# rev02_8.net
KiCad netlist of a schematic drawn in Altium Designer
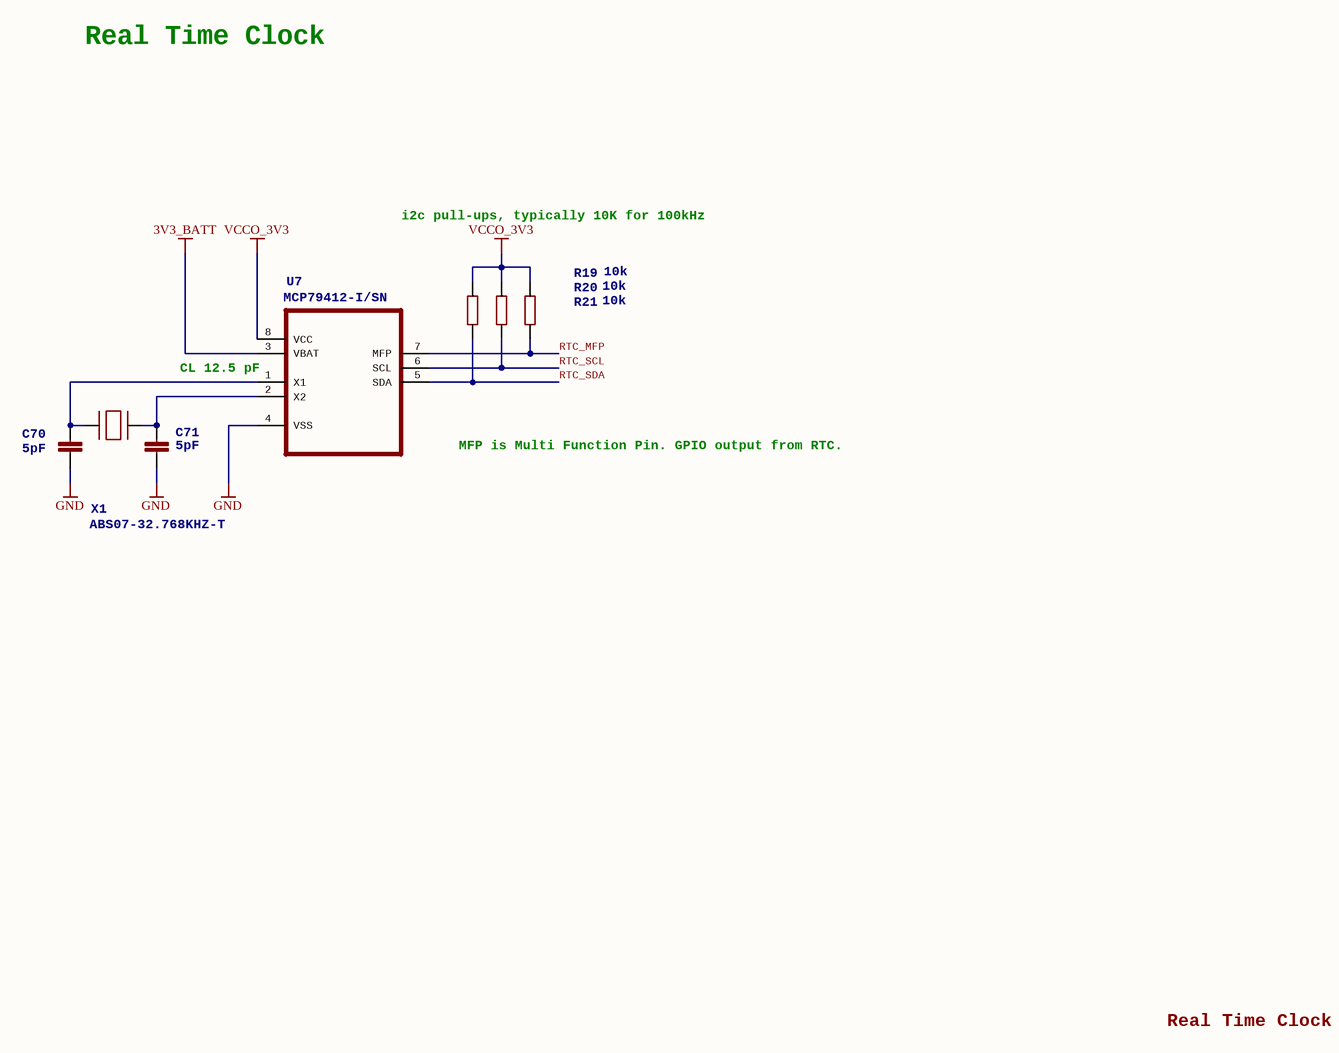
[diagram p0: rev02_8.SchDoc]

(export (version "E")
  (design (tool "Eeschema 10.0.6"))
  (components
    (comp (ref "C70")
      (value "5pF")
      (footprint "C_0402")
      (description "0402 CAPACITOR")
      (libsource (lib "resistor") (part "C-EUC0402"))
    )
    (comp (ref "C71")
      (value "5pF")
      (footprint "C_0402")
      (description "0402 CAPACITOR")
      (libsource (lib "resistor") (part "C-EUC0402"))
    )
    (comp (ref "R19")
      (value "10k")
      (footprint "R_0402")
      (description "0402 Resistor 5%")
      (libsource (lib "resistor") (part "R-EU_R0402"))
    )
    (comp (ref "R20")
      (value "10k")
      (footprint "R_0402")
      (description "0402 Resistor 5%")
      (libsource (lib "resistor") (part "R-EU_R0402"))
    )
    (comp (ref "R21")
      (value "10k")
      (footprint "R_0402")
      (description "0402 Resistor 5%")
      (libsource (lib "resistor") (part "R-EU_R0402"))
    )
    (comp (ref "U7")
      (value "MCP79412-I/SN")
      (footprint "SOIC127P600X175-8N")
      (description "RTCC, I2C, 1K EE, 64B SRAM, 8SOIC")
      (fields (field (name ">NAME") "U7"))
      (libsource (lib "MCP79412") (part "MCP79412-I/SN"))
    )
    (comp (ref "X1")
      (value "ABS07-32.768KHZ-T")
      (footprint "XTAL3215")
      (description "Crystal 32.768kHz")
      (fields (field (name ">NAME") "X1"))
      (libsource (lib "adafruit") (part "XTAL-3.2X1.5"))
    )
  )
  (nets
    (net (code "1") (name "/RTC_MFP") (class "Default")
      (node (ref "R21") (pin "2") (pinfunction "2_2") (pintype "passive"))
      (node (ref "U7") (pin "7") (pinfunction "MFP_7") (pintype "passive"))
    )
    (net (code "2") (name "/RTC_SCL") (class "Default")
      (node (ref "R20") (pin "2") (pinfunction "2_2") (pintype "passive"))
      (node (ref "U7") (pin "6") (pinfunction "SCL_6") (pintype "passive"))
    )
    (net (code "3") (name "/RTC_SDA") (class "Default")
      (node (ref "R19") (pin "2") (pinfunction "2_2") (pintype "passive"))
      (node (ref "U7") (pin "5") (pinfunction "SDA_5") (pintype "passive"))
    )
    (net (code "4") (name "3V3_BATT") (class "Default")
      (node (ref "U7") (pin "3") (pinfunction "VBAT_3") (pintype "power_in"))
    )
    (net (code "5") (name "GND") (class "Default")
      (node (ref "C70") (pin "1") (pinfunction "1_1") (pintype "passive"))
      (node (ref "C71") (pin "1") (pinfunction "1_1") (pintype "passive"))
      (node (ref "U7") (pin "4") (pinfunction "VSS_4") (pintype "power_in"))
    )
    (net (code "6") (name "Net-(U7-X1)") (class "Default")
      (node (ref "C70") (pin "2") (pinfunction "2_2") (pintype "passive"))
      (node (ref "U7") (pin "1") (pinfunction "X1_1") (pintype "passive"))
      (node (ref "X1") (pin "P$1") (pinfunction "P$1_P$1") (pintype "passive"))
    )
    (net (code "7") (name "Net-(U7-X2)") (class "Default")
      (node (ref "C71") (pin "2") (pinfunction "2_2") (pintype "passive"))
      (node (ref "U7") (pin "2") (pinfunction "X2_2") (pintype "passive"))
      (node (ref "X1") (pin "P$2") (pinfunction "P$2_P$2") (pintype "passive"))
    )
    (net (code "8") (name "VCCO_3V3") (class "Default")
      (node (ref "R19") (pin "1") (pinfunction "1_1") (pintype "passive"))
      (node (ref "R20") (pin "1") (pinfunction "1_1") (pintype "passive"))
      (node (ref "R21") (pin "1") (pinfunction "1_1") (pintype "passive"))
      (node (ref "U7") (pin "8") (pinfunction "VCC_8") (pintype "power_in"))
    )
  )
)
